# Sheet1.net
KiCad netlist of a schematic drawn in Altium Designer
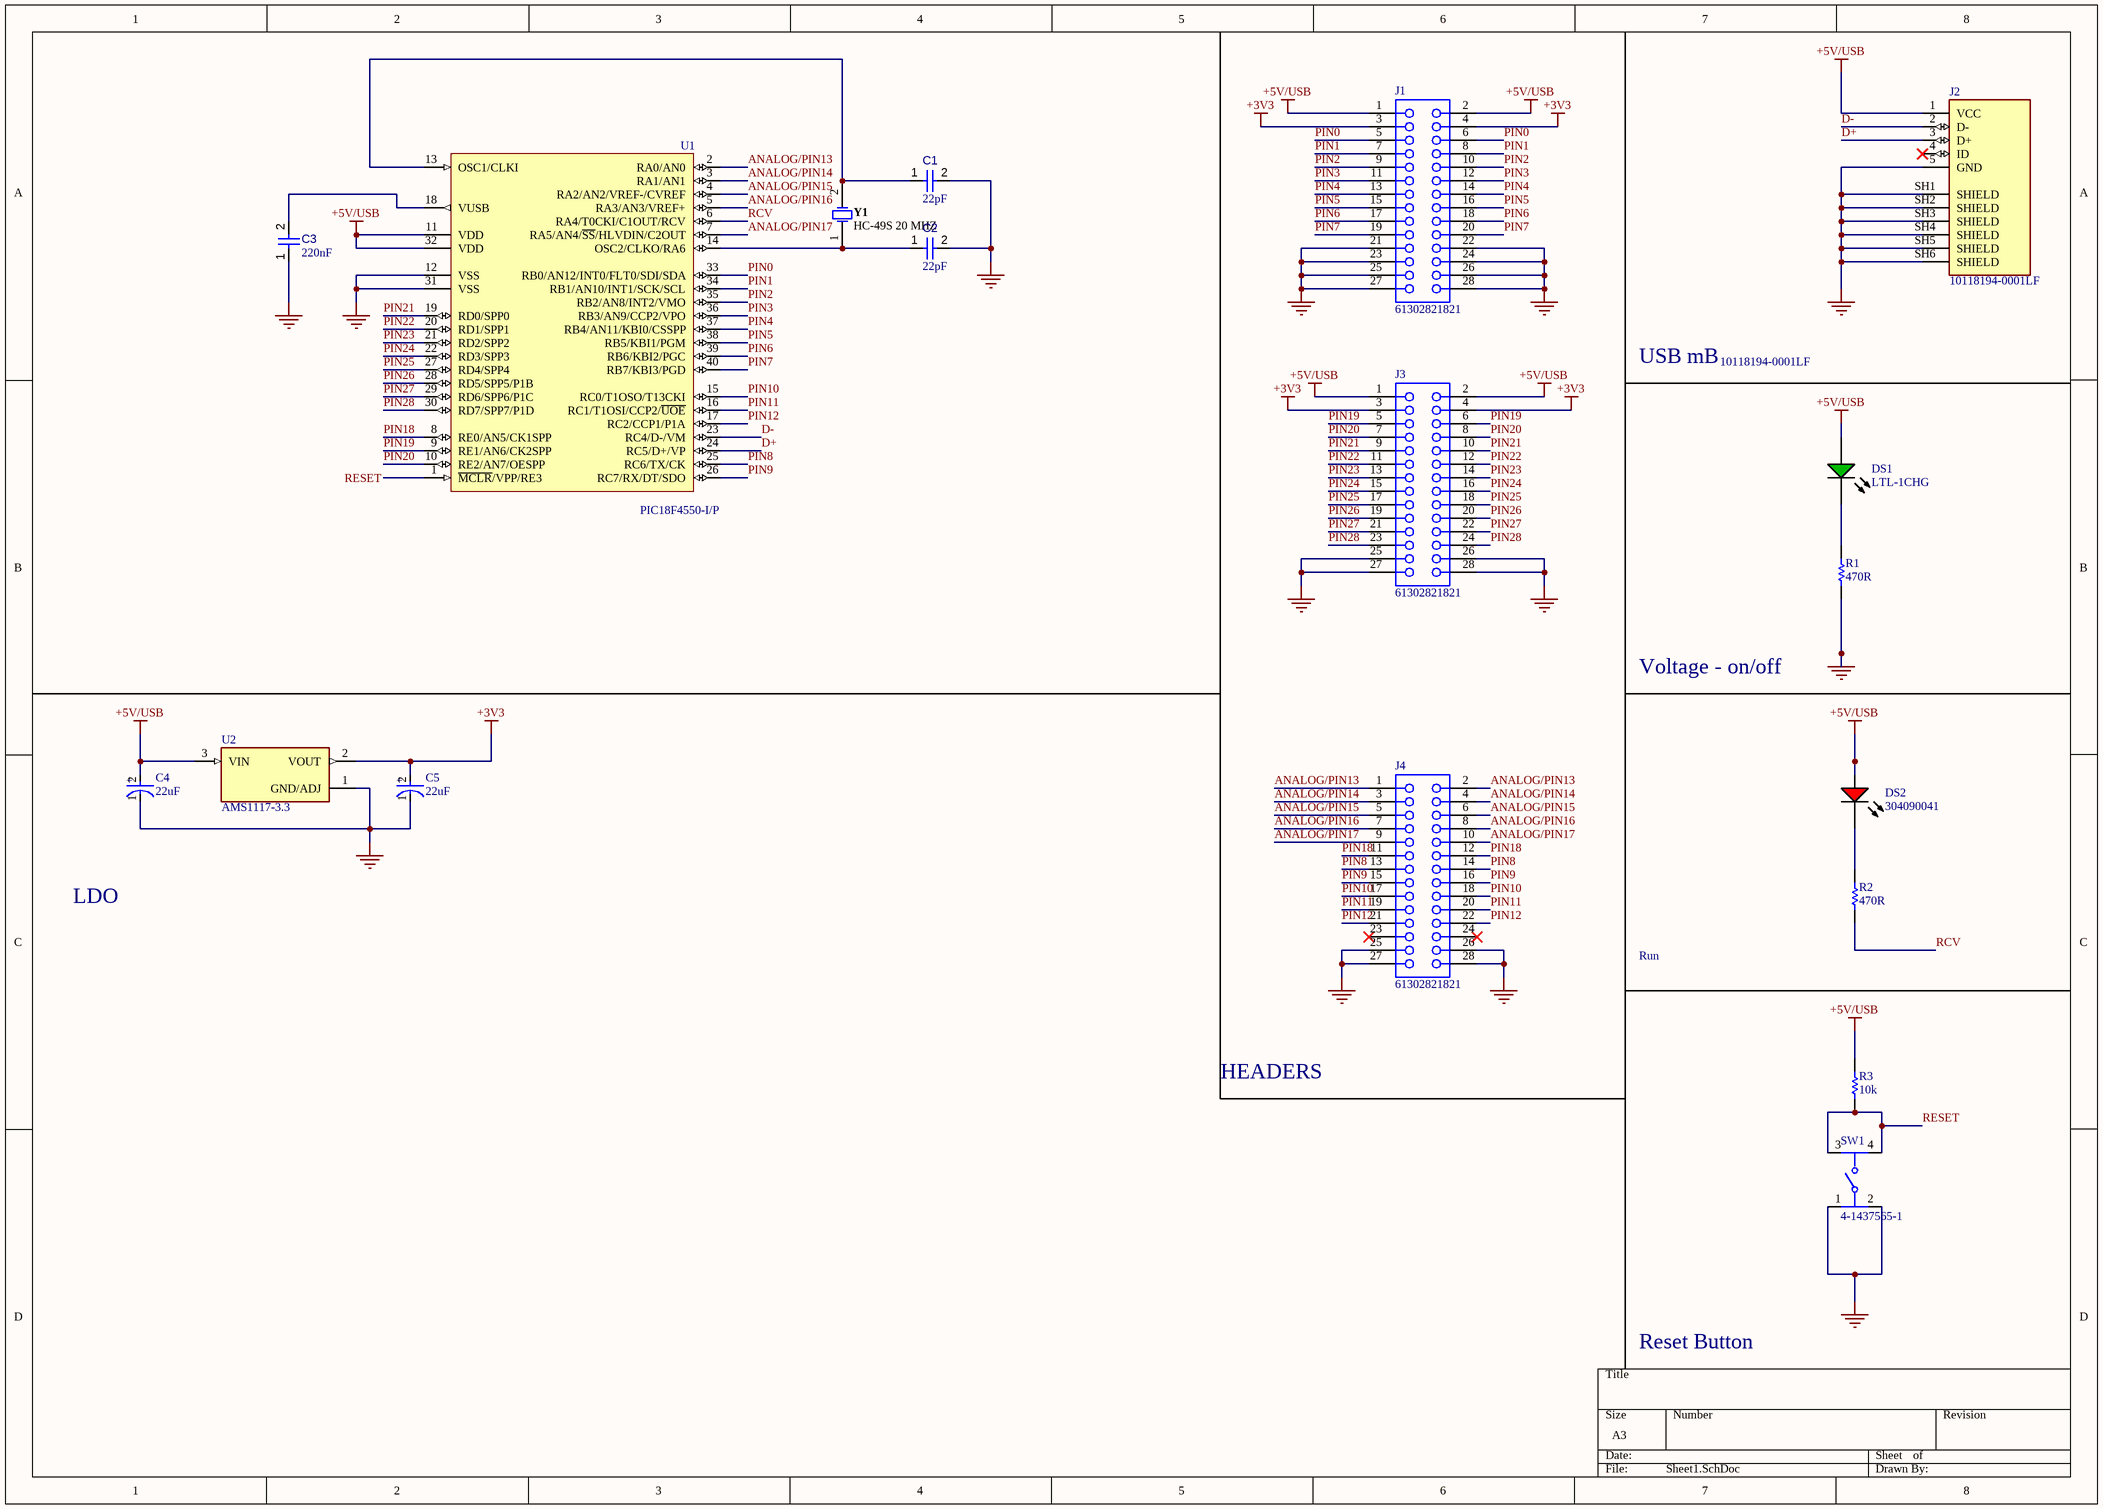
[diagram p0: Sheet1.SchDoc]

(export (version "E")
  (design (tool "Eeschema 10.0.6"))
  (components
    (comp (ref "C1")
      (value "22pF")
      (footprint "CAPC0805(2012)145_L")
      (description "Chip Capacitor 0805")
      (fields (field (name "TOLERANCE") "10%") (field (name "Comment") "Capacitor 47µF +/-40% 6.3V 0805"))
      (libsource (lib "Przemysław Ziencik") (part "CAP-NP-2"))
    )
    (comp (ref "C2")
      (value "22pF")
      (footprint "CAPC0805(2012)145_L")
      (description "Chip Capacitor 0805")
      (fields (field (name "TOLERANCE") "10%") (field (name "Comment") "Capacitor 47µF +/-40% 6.3V 0805"))
      (libsource (lib "Przemysław Ziencik") (part "CAP-NP-2"))
    )
    (comp (ref "C3")
      (value "220nF")
      (footprint "CAPC0805(2012)145_L")
      (description "Chip Capacitor 0805")
      (fields (field (name "TOLERANCE") "10%") (field (name "Comment") "Capacitor 47µF +/-40% 6.3V 0805"))
      (libsource (lib "Przemysław Ziencik") (part "CAP-NP-2"))
    )
    (comp (ref "C4")
      (value "22uF")
      (footprint "FP-TAJA-MFG")
      (description "22uF 10V  ±10% 3Ω 1206  SMD Tantalum Capacitor")
      (fields (field (name "TOLERANCE") "10%") (field (name "VOLTAGE") "10V"))
      (libsource (lib "Altium Content Vault") (part "203bc49f2ac43e59fd269a8c329ed05"))
    )
    (comp (ref "C5")
      (value "22uF")
      (footprint "FP-TAJA-MFG")
      (description "22uF 10V  ±10% 3Ω 1206  SMD Tantalum Capacitor")
      (fields (field (name "TOLERANCE") "10%") (field (name "VOLTAGE") "10V"))
      (libsource (lib "Altium Content Vault") (part "203bc49f2ac43e59fd269a8c329ed05"))
    )
    (comp (ref "DS1")
      (value "LTL-1CHG")
      (footprint "LTST-LTL-1CHG-2")
      (description "LED Uni-Color Green, 100 mW, 30 mA, -55 to 100 degC, 2-Pin THD, RoHS, Bulk")
      (fields (field (name "POWER") "100mW") (field (name "MANUFACTURER") "Lite-On"))
      (libsource (lib "Przemysław Ziencik") (part "LED-GREEN-AK-2"))
    )
    (comp (ref "DS2")
      (value "304090041")
      (footprint "LED-2P-2.28-3MM_A")
      (description "Red LED, 80 mW, 30 mA, -25 to 85 degC, 2-Pin THD")
      (fields (field (name "MANUFACTURER") "Shenzhen CGX"))
      (libsource (lib "Przemysław Ziencik") (part "LED-RED-AK-2"))
    )
    (comp (ref "J1")
      (value "61302821821")
      (footprint "61302821821")
      (libsource (lib "Altium Content Vault") (part "Header_Female_2R_28P"))
    )
    (comp (ref "J2")
      (value "10118194-0001LF")
      (footprint "AMPHENOL_10118194-0001LF")
      (description "Micro USB, Input Output Connectors, B TYPE RECEPTACLE with flange")
      (fields (field (name "MF") "Amphenol ICC"))
      (libsource (lib "10118194-0001LF") (part "10118194-0001LF"))
    )
    (comp (ref "J3")
      (value "61302821821")
      (footprint "61302821821")
      (libsource (lib "Altium Content Vault") (part "Header_Female_2R_28P"))
    )
    (comp (ref "J4")
      (value "61302821821")
      (footprint "61302821821")
      (libsource (lib "Altium Content Vault") (part "Header_Female_2R_28P"))
    )
    (comp (ref "R1")
      (value "470R")
      (footprint "RESC3216X70X50LL05T20")
      (fields (field (name "MANUFACTURER") "Panasonic") (field (name "PART NUMBER") "ERJ8ENF4700V"))
      (libsource (lib "Altium Content Vault") (part "RES"))
    )
    (comp (ref "R2")
      (value "470R")
      (footprint "RESC3216X70X50LL05T20")
      (fields (field (name "MANUFACTURER") "Panasonic") (field (name "PART NUMBER") "ERJ8ENF4700V"))
      (libsource (lib "Altium Content Vault") (part "RES"))
    )
    (comp (ref "R3")
      (value "10k")
      (footprint "RESC3216X70X50LL05T20")
      (fields (field (name "MANUFACTURER") "Panasonic") (field (name "PART NUMBER") "ERJ8ENF4700V"))
      (libsource (lib "Altium Content Vault") (part "RES"))
    )
    (comp (ref "SW1")
      (value "4-1437565-1")
      (footprint "FP-4-1437565-1-MFG")
      (description "SWITCH TACTILE SPST-NO 0.05A 24V")
      (fields
        (field (name "MANUFACTURER") "TE Connectivity")
        (field (name "OCTOPART") "https://octopart.com/fsm4jsma-te+connectivity-55488004")
      )
      (libsource (lib "Altium Content Vault") (part "b8895f3f4cefb76e1819d2863dba89b"))
    )
    (comp (ref "U1")
      (value "PIC18F4550-I/P")
      (footprint "PDIP600-P40")
      (libsource (lib "Altium Content Vault") (part "MC-8B-18F4550-IL40"))
    )
    (comp (ref "U2")
      (value "AMS1117-3.3")
      (footprint "SOT229P700X180-4N")
      (description "Sot223/Pkg 1-Amp 3.3-Volt Low Drop Out Voltage Regulatator")
      (fields (field (name "MF") "Advanced Monolithic Systems"))
      (libsource (lib "AMS1117-3.3") (part "AMS1117-3.3"))
    )
    (comp (ref "Y1")
      (value "HC-49S 20 MHZ")
      (footprint "JPY-HC-49US")
      (description "Crystal, 16 MHz, +/- 30 ppm, 18 pF, -20 to 70 degC, 2-Pin THD")
      (fields (field (name "MANUFACTURER") "Jing peng yuan"))
      (libsource (lib "Przemysław Ziencik") (part "XTAL-1-2-2"))
    )
  )
  (nets
    (net (code "1") (name "+3V3") (class "Default")
      (node (ref "C5") (pin "2") (pinfunction "A_2") (pintype "passive"))
      (node (ref "J1") (pin "3") (pinfunction "3_3") (pintype "passive"))
      (node (ref "J1") (pin "4") (pinfunction "4_4") (pintype "passive"))
      (node (ref "J3") (pin "3") (pinfunction "3_3") (pintype "passive"))
      (node (ref "J3") (pin "4") (pinfunction "4_4") (pintype "passive"))
      (node (ref "U2") (pin "2") (pinfunction "VOUT_2") (pintype "output"))
    )
    (net (code "2") (name "+5V{slash}USB") (class "Default")
      (node (ref "C4") (pin "2") (pinfunction "A_2") (pintype "passive"))
      (node (ref "DS1") (pin "1") (pinfunction "A_1") (pintype "passive"))
      (node (ref "DS2") (pin "1") (pinfunction "A_1") (pintype "passive"))
      (node (ref "J1") (pin "1") (pinfunction "1_1") (pintype "passive"))
      (node (ref "J1") (pin "2") (pinfunction "2_2") (pintype "passive"))
      (node (ref "J2") (pin "1") (pinfunction "VCC_1") (pintype "power_in"))
      (node (ref "J3") (pin "1") (pinfunction "1_1") (pintype "passive"))
      (node (ref "J3") (pin "2") (pinfunction "2_2") (pintype "passive"))
      (node (ref "R3") (pin "2") (pinfunction "2_2") (pintype "passive"))
      (node (ref "U1") (pin "11") (pinfunction "VDD_11") (pintype "power_in"))
      (node (ref "U1") (pin "32") (pinfunction "VDD_32") (pintype "power_in"))
      (node (ref "U2") (pin "3") (pinfunction "VIN_3") (pintype "input"))
    )
    (net (code "3") (name "/ANALOG{slash}PIN13") (class "Default")
      (node (ref "J4") (pin "1") (pinfunction "1_1") (pintype "passive"))
      (node (ref "J4") (pin "2") (pinfunction "2_2") (pintype "passive"))
      (node (ref "U1") (pin "2") (pinfunction "RA0/AN0_2") (pintype "bidirectional"))
    )
    (net (code "4") (name "/ANALOG{slash}PIN14") (class "Default")
      (node (ref "J4") (pin "3") (pinfunction "3_3") (pintype "passive"))
      (node (ref "J4") (pin "4") (pinfunction "4_4") (pintype "passive"))
      (node (ref "U1") (pin "3") (pinfunction "RA1/AN1_3") (pintype "bidirectional"))
    )
    (net (code "5") (name "/ANALOG{slash}PIN15") (class "Default")
      (node (ref "J4") (pin "5") (pinfunction "5_5") (pintype "passive"))
      (node (ref "J4") (pin "6") (pinfunction "6_6") (pintype "passive"))
      (node (ref "U1") (pin "4") (pinfunction "RA2/AN2/VREF-/CVREF_4") (pintype "bidirectional"))
    )
    (net (code "6") (name "/ANALOG{slash}PIN16") (class "Default")
      (node (ref "J4") (pin "7") (pinfunction "7_7") (pintype "passive"))
      (node (ref "J4") (pin "8") (pinfunction "8_8") (pintype "passive"))
      (node (ref "U1") (pin "5") (pinfunction "RA3/AN3/VREF+_5") (pintype "bidirectional"))
    )
    (net (code "7") (name "/ANALOG{slash}PIN17") (class "Default")
      (node (ref "J4") (pin "10") (pinfunction "10_10") (pintype "passive"))
      (node (ref "J4") (pin "9") (pinfunction "9_9") (pintype "passive"))
      (node (ref "U1") (pin "7") (pinfunction "RA5/AN4/~{SS}/HLVDIN/C2OUT_7") (pintype "bidirectional"))
    )
    (net (code "8") (name "/D+") (class "Default")
      (node (ref "J2") (pin "3") (pinfunction "D+_3") (pintype "bidirectional"))
      (node (ref "U1") (pin "24") (pinfunction "RC5/D+/VP_24") (pintype "bidirectional"))
    )
    (net (code "9") (name "/D-") (class "Default")
      (node (ref "J2") (pin "2") (pinfunction "D-_2") (pintype "bidirectional"))
      (node (ref "U1") (pin "23") (pinfunction "RC4/D-/VM_23") (pintype "bidirectional"))
    )
    (net (code "10") (name "/PIN0") (class "Default")
      (node (ref "J1") (pin "5") (pinfunction "5_5") (pintype "passive"))
      (node (ref "J1") (pin "6") (pinfunction "6_6") (pintype "passive"))
      (node (ref "U1") (pin "33") (pinfunction "RB0/AN12/INT0/FLT0/SDI/SDA_33") (pintype "bidirectional"))
    )
    (net (code "11") (name "/PIN1") (class "Default")
      (node (ref "J1") (pin "7") (pinfunction "7_7") (pintype "passive"))
      (node (ref "J1") (pin "8") (pinfunction "8_8") (pintype "passive"))
      (node (ref "U1") (pin "34") (pinfunction "RB1/AN10/INT1/SCK/SCL_34") (pintype "bidirectional"))
    )
    (net (code "12") (name "/PIN2") (class "Default")
      (node (ref "J1") (pin "10") (pinfunction "10_10") (pintype "passive"))
      (node (ref "J1") (pin "9") (pinfunction "9_9") (pintype "passive"))
      (node (ref "U1") (pin "35") (pinfunction "RB2/AN8/INT2/VMO_35") (pintype "bidirectional"))
    )
    (net (code "13") (name "/PIN3") (class "Default")
      (node (ref "J1") (pin "11") (pinfunction "11_11") (pintype "passive"))
      (node (ref "J1") (pin "12") (pinfunction "12_12") (pintype "passive"))
      (node (ref "U1") (pin "36") (pinfunction "RB3/AN9/CCP2/VPO_36") (pintype "bidirectional"))
    )
    (net (code "14") (name "/PIN4") (class "Default")
      (node (ref "J1") (pin "13") (pinfunction "13_13") (pintype "passive"))
      (node (ref "J1") (pin "14") (pinfunction "14_14") (pintype "passive"))
      (node (ref "U1") (pin "37") (pinfunction "RB4/AN11/KBI0/CSSPP_37") (pintype "bidirectional"))
    )
    (net (code "15") (name "/PIN5") (class "Default")
      (node (ref "J1") (pin "15") (pinfunction "15_15") (pintype "passive"))
      (node (ref "J1") (pin "16") (pinfunction "16_16") (pintype "passive"))
      (node (ref "U1") (pin "38") (pinfunction "RB5/KBI1/PGM_38") (pintype "bidirectional"))
    )
    (net (code "16") (name "/PIN6") (class "Default")
      (node (ref "J1") (pin "17") (pinfunction "17_17") (pintype "passive"))
      (node (ref "J1") (pin "18") (pinfunction "18_18") (pintype "passive"))
      (node (ref "U1") (pin "39") (pinfunction "RB6/KBI2/PGC_39") (pintype "bidirectional"))
    )
    (net (code "17") (name "/PIN7") (class "Default")
      (node (ref "J1") (pin "19") (pinfunction "19_19") (pintype "passive"))
      (node (ref "J1") (pin "20") (pinfunction "20_20") (pintype "passive"))
      (node (ref "U1") (pin "40") (pinfunction "RB7/KBI3/PGD_40") (pintype "bidirectional"))
    )
    (net (code "18") (name "/PIN8") (class "Default")
      (node (ref "J4") (pin "13") (pinfunction "13_13") (pintype "passive"))
      (node (ref "J4") (pin "14") (pinfunction "14_14") (pintype "passive"))
      (node (ref "U1") (pin "25") (pinfunction "RC6/TX/CK_25") (pintype "bidirectional"))
    )
    (net (code "19") (name "/PIN9") (class "Default")
      (node (ref "J4") (pin "15") (pinfunction "15_15") (pintype "passive"))
      (node (ref "J4") (pin "16") (pinfunction "16_16") (pintype "passive"))
      (node (ref "U1") (pin "26") (pinfunction "RC7/RX/DT/SDO_26") (pintype "bidirectional"))
    )
    (net (code "20") (name "/PIN10") (class "Default")
      (node (ref "J4") (pin "17") (pinfunction "17_17") (pintype "passive"))
      (node (ref "J4") (pin "18") (pinfunction "18_18") (pintype "passive"))
      (node (ref "U1") (pin "15") (pinfunction "RC0/T1OSO/T13CKI_15") (pintype "bidirectional"))
    )
    (net (code "21") (name "/PIN11") (class "Default")
      (node (ref "J4") (pin "19") (pinfunction "19_19") (pintype "passive"))
      (node (ref "J4") (pin "20") (pinfunction "20_20") (pintype "passive"))
      (node (ref "U1") (pin "16") (pinfunction "RC1/T1OSI/CCP2/~{UOE}_16") (pintype "bidirectional"))
    )
    (net (code "22") (name "/PIN12") (class "Default")
      (node (ref "J4") (pin "21") (pinfunction "21_21") (pintype "passive"))
      (node (ref "J4") (pin "22") (pinfunction "22_22") (pintype "passive"))
      (node (ref "U1") (pin "17") (pinfunction "RC2/CCP1/P1A_17") (pintype "bidirectional"))
    )
    (net (code "23") (name "/PIN18") (class "Default")
      (node (ref "J4") (pin "11") (pinfunction "11_11") (pintype "passive"))
      (node (ref "J4") (pin "12") (pinfunction "12_12") (pintype "passive"))
      (node (ref "U1") (pin "8") (pinfunction "RE0/AN5/CK1SPP_8") (pintype "bidirectional"))
    )
    (net (code "24") (name "/PIN19") (class "Default")
      (node (ref "J3") (pin "5") (pinfunction "5_5") (pintype "passive"))
      (node (ref "J3") (pin "6") (pinfunction "6_6") (pintype "passive"))
      (node (ref "U1") (pin "9") (pinfunction "RE1/AN6/CK2SPP_9") (pintype "bidirectional"))
    )
    (net (code "25") (name "/PIN20") (class "Default")
      (node (ref "J3") (pin "7") (pinfunction "7_7") (pintype "passive"))
      (node (ref "J3") (pin "8") (pinfunction "8_8") (pintype "passive"))
      (node (ref "U1") (pin "10") (pinfunction "RE2/AN7/OESPP_10") (pintype "bidirectional"))
    )
    (net (code "26") (name "/PIN21") (class "Default")
      (node (ref "J3") (pin "10") (pinfunction "10_10") (pintype "passive"))
      (node (ref "J3") (pin "9") (pinfunction "9_9") (pintype "passive"))
      (node (ref "U1") (pin "19") (pinfunction "RD0/SPP0_19") (pintype "bidirectional"))
    )
    (net (code "27") (name "/PIN22") (class "Default")
      (node (ref "J3") (pin "11") (pinfunction "11_11") (pintype "passive"))
      (node (ref "J3") (pin "12") (pinfunction "12_12") (pintype "passive"))
      (node (ref "U1") (pin "20") (pinfunction "RD1/SPP1_20") (pintype "bidirectional"))
    )
    (net (code "28") (name "/PIN23") (class "Default")
      (node (ref "J3") (pin "13") (pinfunction "13_13") (pintype "passive"))
      (node (ref "J3") (pin "14") (pinfunction "14_14") (pintype "passive"))
      (node (ref "U1") (pin "21") (pinfunction "RD2/SPP2_21") (pintype "bidirectional"))
    )
    (net (code "29") (name "/PIN24") (class "Default")
      (node (ref "J3") (pin "15") (pinfunction "15_15") (pintype "passive"))
      (node (ref "J3") (pin "16") (pinfunction "16_16") (pintype "passive"))
      (node (ref "U1") (pin "22") (pinfunction "RD3/SPP3_22") (pintype "bidirectional"))
    )
    (net (code "30") (name "/PIN25") (class "Default")
      (node (ref "J3") (pin "17") (pinfunction "17_17") (pintype "passive"))
      (node (ref "J3") (pin "18") (pinfunction "18_18") (pintype "passive"))
      (node (ref "U1") (pin "27") (pinfunction "RD4/SPP4_27") (pintype "bidirectional"))
    )
    (net (code "31") (name "/PIN26") (class "Default")
      (node (ref "J3") (pin "19") (pinfunction "19_19") (pintype "passive"))
      (node (ref "J3") (pin "20") (pinfunction "20_20") (pintype "passive"))
      (node (ref "U1") (pin "28") (pinfunction "RD5/SPP5/P1B_28") (pintype "bidirectional"))
    )
    (net (code "32") (name "/PIN27") (class "Default")
      (node (ref "J3") (pin "21") (pinfunction "21_21") (pintype "passive"))
      (node (ref "J3") (pin "22") (pinfunction "22_22") (pintype "passive"))
      (node (ref "U1") (pin "29") (pinfunction "RD6/SPP6/P1C_29") (pintype "bidirectional"))
    )
    (net (code "33") (name "/PIN28") (class "Default")
      (node (ref "J3") (pin "23") (pinfunction "23_23") (pintype "passive"))
      (node (ref "J3") (pin "24") (pinfunction "24_24") (pintype "passive"))
      (node (ref "U1") (pin "30") (pinfunction "RD7/SPP7/P1D_30") (pintype "bidirectional"))
    )
    (net (code "34") (name "/RCV") (class "Default")
      (node (ref "R2") (pin "1") (pinfunction "1_1") (pintype "passive"))
      (node (ref "U1") (pin "6") (pinfunction "RA4/T0CKI/C1OUT/RCV_6") (pintype "bidirectional"))
    )
    (net (code "35") (name "/RESET") (class "Default")
      (node (ref "R3") (pin "1") (pinfunction "1_1") (pintype "passive"))
      (node (ref "SW1") (pin "3") (pinfunction "3_3") (pintype "passive"))
      (node (ref "SW1") (pin "4") (pinfunction "4_4") (pintype "passive"))
      (node (ref "U1") (pin "1") (pinfunction "~{MCLR}/VPP/RE3_1") (pintype "input"))
    )
    (net (code "36") (name "GND") (class "Default")
      (node (ref "C1") (pin "2") (pinfunction "2_2") (pintype "passive"))
      (node (ref "C2") (pin "2") (pinfunction "2_2") (pintype "passive"))
      (node (ref "C3") (pin "1") (pinfunction "1_1") (pintype "passive"))
      (node (ref "C4") (pin "1") (pinfunction "C_1") (pintype "passive"))
      (node (ref "C5") (pin "1") (pinfunction "C_1") (pintype "passive"))
      (node (ref "J1") (pin "21") (pinfunction "21_21") (pintype "passive"))
      (node (ref "J1") (pin "22") (pinfunction "22_22") (pintype "passive"))
      (node (ref "J1") (pin "23") (pinfunction "23_23") (pintype "passive"))
      (node (ref "J1") (pin "24") (pinfunction "24_24") (pintype "passive"))
      (node (ref "J1") (pin "25") (pinfunction "25_25") (pintype "passive"))
      (node (ref "J1") (pin "26") (pinfunction "26_26") (pintype "passive"))
      (node (ref "J1") (pin "27") (pinfunction "27_27") (pintype "passive"))
      (node (ref "J1") (pin "28") (pinfunction "28_28") (pintype "passive"))
      (node (ref "J2") (pin "5") (pinfunction "GND_5") (pintype "power_in"))
      (node (ref "J2") (pin "SH1") (pinfunction "SHIELD_SH1") (pintype "passive"))
      (node (ref "J2") (pin "SH2") (pinfunction "SHIELD_SH2") (pintype "passive"))
      (node (ref "J2") (pin "SH3") (pinfunction "SHIELD_SH3") (pintype "passive"))
      (node (ref "J2") (pin "SH4") (pinfunction "SHIELD_SH4") (pintype "passive"))
      (node (ref "J2") (pin "SH5") (pinfunction "SHIELD_SH5") (pintype "passive"))
      (node (ref "J2") (pin "SH6") (pinfunction "SHIELD_SH6") (pintype "passive"))
      (node (ref "J3") (pin "25") (pinfunction "25_25") (pintype "passive"))
      (node (ref "J3") (pin "26") (pinfunction "26_26") (pintype "passive"))
      (node (ref "J3") (pin "27") (pinfunction "27_27") (pintype "passive"))
      (node (ref "J3") (pin "28") (pinfunction "28_28") (pintype "passive"))
      (node (ref "J4") (pin "25") (pinfunction "25_25") (pintype "passive"))
      (node (ref "J4") (pin "26") (pinfunction "26_26") (pintype "passive"))
      (node (ref "J4") (pin "27") (pinfunction "27_27") (pintype "passive"))
      (node (ref "J4") (pin "28") (pinfunction "28_28") (pintype "passive"))
      (node (ref "R1") (pin "1") (pinfunction "1_1") (pintype "passive"))
      (node (ref "SW1") (pin "1") (pinfunction "1_1") (pintype "passive"))
      (node (ref "SW1") (pin "2") (pinfunction "2_2") (pintype "passive"))
      (node (ref "U1") (pin "12") (pinfunction "VSS_12") (pintype "power_in"))
      (node (ref "U1") (pin "31") (pinfunction "VSS_31") (pintype "power_in"))
      (node (ref "U2") (pin "1") (pinfunction "GND/ADJ_1") (pintype "power_in"))
    )
    (net (code "37") (name "Net-(DS1-K)") (class "Default")
      (node (ref "DS1") (pin "2") (pinfunction "K_2") (pintype "passive"))
      (node (ref "R1") (pin "2") (pinfunction "2_2") (pintype "passive"))
    )
    (net (code "38") (name "Net-(DS2-K)") (class "Default")
      (node (ref "DS2") (pin "2") (pinfunction "K_2") (pintype "passive"))
      (node (ref "R2") (pin "2") (pinfunction "2_2") (pintype "passive"))
    )
    (net (code "39") (name "Net-(U1-OSC1{slash}CLKI)") (class "Default")
      (node (ref "C1") (pin "1") (pinfunction "1_1") (pintype "passive"))
      (node (ref "U1") (pin "13") (pinfunction "OSC1/CLKI_13") (pintype "input"))
      (node (ref "Y1") (pin "2") (pinfunction "2_2") (pintype "passive"))
    )
    (net (code "40") (name "Net-(U1-OSC2{slash}CLKO{slash}RA6)") (class "Default")
      (node (ref "C2") (pin "1") (pinfunction "1_1") (pintype "passive"))
      (node (ref "U1") (pin "14") (pinfunction "OSC2/CLKO/RA6_14") (pintype "bidirectional"))
      (node (ref "Y1") (pin "1") (pinfunction "1_1") (pintype "passive"))
    )
    (net (code "41") (name "Net-(U1-VUSB)") (class "Default")
      (node (ref "C3") (pin "2") (pinfunction "2_2") (pintype "passive"))
      (node (ref "U1") (pin "18") (pinfunction "VUSB_18") (pintype "output"))
    )
    (net (code "42") (name "unconnected-(J2-ID-Pad4)") (class "Default")
      (node (ref "J2") (pin "4") (pinfunction "ID_4") (pintype "bidirectional+no_connect"))
    )
    (net (code "43") (name "unconnected-(J4-Pad23)") (class "Default")
      (node (ref "J4") (pin "23") (pinfunction "23_23") (pintype "passive+no_connect"))
    )
    (net (code "44") (name "unconnected-(J4-Pad24)") (class "Default")
      (node (ref "J4") (pin "24") (pinfunction "24_24") (pintype "passive+no_connect"))
    )
  )
)
